# Crowtail-_LoRa_RA-08H-V1_2.net
KiCad netlist of a schematic drawn in EAGLE
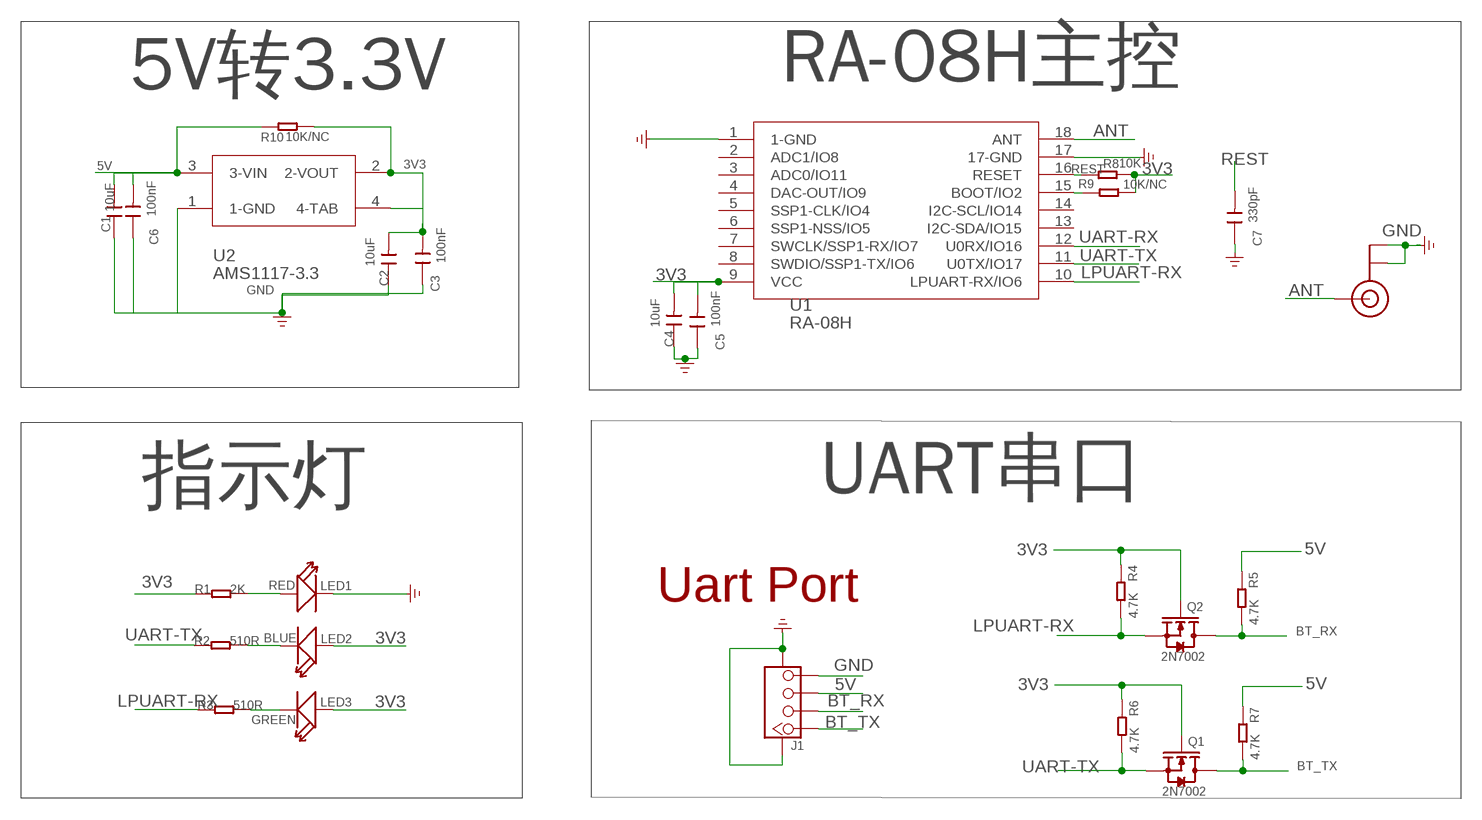
[diagram p0: schematic, sheet 1]

(export (version "E")
  (design (tool "Eeschema 10.0.6"))
  (components
    (comp (ref "C1")
      (value "10uF")
      (footprint "eagle-import:C0805")
      (libsource (lib "eagle-import") (part "C-0805"))
    )
    (comp (ref "C2")
      (value "10uF")
      (footprint "eagle-import:C0805")
      (libsource (lib "eagle-import") (part "C-0805"))
    )
    (comp (ref "C3")
      (value "100nF")
      (footprint "eagle-import:C0603")
      (libsource (lib "eagle-import") (part "C-0603"))
    )
    (comp (ref "C4")
      (value "10uF")
      (footprint "eagle-import:C0805")
      (libsource (lib "eagle-import") (part "C-0805"))
    )
    (comp (ref "C5")
      (value "100nF")
      (footprint "eagle-import:C0603")
      (libsource (lib "eagle-import") (part "C-0603"))
    )
    (comp (ref "C6")
      (value "100nF")
      (footprint "eagle-import:C0603")
      (libsource (lib "eagle-import") (part "C-0603"))
    )
    (comp (ref "C7")
      (value "330pF")
      (footprint "eagle-import:C0603")
      (libsource (lib "eagle-import") (part "C-0603"))
    )
    (comp (ref "J1")
      (value "TWIG-4P-2.0-SMD-FEMALE-REINFORCE'90D'")
      (footprint "eagle-import:4P-SMD-2.0-90D")
      (libsource (lib "eagle-import") (part "TWIG-4P-2.0-SMD-FEMALE-REINFORCE'90D'"))
    )
    (comp (ref "J2")
      (value "U.FL")
      (footprint "eagle-import:U.FL")
      (libsource (lib "eagle-import") (part "U.FL"))
    )
    (comp (ref "LED1")
      (value "RED")
      (footprint "eagle-import:LED-0603")
      (libsource (lib "eagle-import") (part "LED'0603'"))
    )
    (comp (ref "LED2")
      (value "BLUE")
      (footprint "eagle-import:LED-0603")
      (libsource (lib "eagle-import") (part "LED'0603'"))
    )
    (comp (ref "LED3")
      (value "GREEN")
      (footprint "eagle-import:LED-0603")
      (libsource (lib "eagle-import") (part "LED'0603'"))
    )
    (comp (ref "Q1")
      (value "2N7002")
      (footprint "eagle-import:SOT23")
      (libsource (lib "eagle-import") (part "MOSFET-N'SOT23'"))
    )
    (comp (ref "Q2")
      (value "2N7002")
      (footprint "eagle-import:SOT23")
      (libsource (lib "eagle-import") (part "MOSFET-N'SOT23'"))
    )
    (comp (ref "R1")
      (value "2K")
      (footprint "eagle-import:0603")
      (libsource (lib "eagle-import") (part "R-0603"))
    )
    (comp (ref "R2")
      (value "510R")
      (footprint "eagle-import:0603")
      (libsource (lib "eagle-import") (part "R-0603"))
    )
    (comp (ref "R3")
      (value "510R")
      (footprint "eagle-import:0603")
      (libsource (lib "eagle-import") (part "R-0603"))
    )
    (comp (ref "R4")
      (value "4.7K")
      (footprint "eagle-import:DISCRETE_R0603")
      (libsource (lib "eagle-import") (part "DISCRETE_R-0603"))
    )
    (comp (ref "R5")
      (value "4.7K")
      (footprint "eagle-import:DISCRETE_R0603")
      (libsource (lib "eagle-import") (part "DISCRETE_R-0603"))
    )
    (comp (ref "R6")
      (value "4.7K")
      (footprint "eagle-import:DISCRETE_R0603")
      (libsource (lib "eagle-import") (part "DISCRETE_R-0603"))
    )
    (comp (ref "R7")
      (value "4.7K")
      (footprint "eagle-import:DISCRETE_R0603")
      (libsource (lib "eagle-import") (part "DISCRETE_R-0603"))
    )
    (comp (ref "R8")
      (value "10K")
      (footprint "eagle-import:DISCRETE_R0603")
      (libsource (lib "eagle-import") (part "DISCRETE_R-0603"))
    )
    (comp (ref "R9")
      (value "10K/NC")
      (footprint "eagle-import:DISCRETE_R0603")
      (libsource (lib "eagle-import") (part "DISCRETE_R-0603"))
    )
    (comp (ref "R10")
      (value "10K/NC")
      (footprint "eagle-import:DISCRETE_R0603")
      (libsource (lib "eagle-import") (part "DISCRETE_R-0603"))
    )
    (comp (ref "U1")
      (value "RA-08H")
      (footprint "eagle-import:RA-08H-SMD-18")
      (libsource (lib "eagle-import") (part "RA-08H"))
    )
    (comp (ref "U2")
      (value "AMS1117-3.3")
      (footprint "eagle-import:AMS1117-3.3-SOT223")
      (libsource (lib "eagle-import") (part "AMS1117-3.3"))
    )
  )
  (nets
    (net (code "1") (name "/3V3") (class "Default")
      (node (ref "C2") (pin "2") (pinfunction "2_2") (pintype "passive"))
      (node (ref "C3") (pin "2") (pinfunction "2_2") (pintype "passive"))
      (node (ref "C4") (pin "2") (pinfunction "2_2") (pintype "passive"))
      (node (ref "C5") (pin "2") (pinfunction "2_2") (pintype "passive"))
      (node (ref "LED2") (pin "+") (pinfunction "+_+") (pintype "passive"))
      (node (ref "LED3") (pin "+") (pinfunction "+_+") (pintype "passive"))
      (node (ref "Q1") (pin "1") (pinfunction "G_1") (pintype "passive"))
      (node (ref "Q2") (pin "1") (pinfunction "G_1") (pintype "passive"))
      (node (ref "R1") (pin "1") (pinfunction "1_1") (pintype "passive"))
      (node (ref "R10") (pin "2") (pinfunction "2_2") (pintype "passive"))
      (node (ref "R4") (pin "1") (pinfunction "1_1") (pintype "passive"))
      (node (ref "R6") (pin "1") (pinfunction "1_1") (pintype "passive"))
      (node (ref "R8") (pin "2") (pinfunction "2_2") (pintype "passive"))
      (node (ref "R9") (pin "2") (pinfunction "2_2") (pintype "passive"))
      (node (ref "U1") (pin "9") (pinfunction "VCC_9") (pintype "bidirectional"))
      (node (ref "U2") (pin "2") (pinfunction "2-VOUT_2") (pintype "bidirectional"))
      (node (ref "U2") (pin "4") (pinfunction "4-TAB_4") (pintype "bidirectional"))
    )
    (net (code "2") (name "/5V") (class "Default")
      (node (ref "C1") (pin "2") (pinfunction "2_2") (pintype "passive"))
      (node (ref "C6") (pin "2") (pinfunction "2_2") (pintype "passive"))
      (node (ref "J1") (pin "3") (pinfunction "3_3") (pintype "bidirectional"))
      (node (ref "R10") (pin "1") (pinfunction "1_1") (pintype "passive"))
      (node (ref "R5") (pin "1") (pinfunction "1_1") (pintype "passive"))
      (node (ref "R7") (pin "1") (pinfunction "1_1") (pintype "passive"))
      (node (ref "U2") (pin "3") (pinfunction "3-VIN_3") (pintype "bidirectional"))
    )
    (net (code "3") (name "/ANT") (class "Default")
      (node (ref "J2") (pin "P$3") (pinfunction "SIGNAL_P$3") (pintype "bidirectional"))
      (node (ref "U1") (pin "18") (pinfunction "ANT_18") (pintype "bidirectional"))
    )
    (net (code "4") (name "/BT_RX") (class "Default")
      (node (ref "J1") (pin "2") (pinfunction "2_2") (pintype "bidirectional"))
      (node (ref "Q2") (pin "3") (pinfunction "D_3") (pintype "passive"))
      (node (ref "R5") (pin "2") (pinfunction "2_2") (pintype "passive"))
    )
    (net (code "5") (name "/BT_TX") (class "Default")
      (node (ref "J1") (pin "1") (pinfunction "1_1") (pintype "bidirectional"))
      (node (ref "Q1") (pin "3") (pinfunction "D_3") (pintype "passive"))
      (node (ref "R7") (pin "2") (pinfunction "2_2") (pintype "passive"))
    )
    (net (code "6") (name "/LPUART-RX") (class "Default")
      (node (ref "Q2") (pin "2") (pinfunction "S_2") (pintype "passive"))
      (node (ref "R3") (pin "1") (pinfunction "1_1") (pintype "passive"))
      (node (ref "R4") (pin "2") (pinfunction "2_2") (pintype "passive"))
      (node (ref "U1") (pin "10") (pinfunction "LPUART-RX/IO6_10") (pintype "bidirectional"))
    )
    (net (code "7") (name "/REST") (class "Default")
      (node (ref "C7") (pin "2") (pinfunction "2_2") (pintype "passive"))
      (node (ref "R8") (pin "1") (pinfunction "1_1") (pintype "passive"))
      (node (ref "U1") (pin "16") (pinfunction "RESET_16") (pintype "bidirectional"))
    )
    (net (code "8") (name "/UART-RX") (class "Default")
      (node (ref "U1") (pin "12") (pinfunction "U0RX/IO16_12") (pintype "bidirectional"))
    )
    (net (code "9") (name "/UART-TX") (class "Default")
      (node (ref "Q1") (pin "2") (pinfunction "S_2") (pintype "passive"))
      (node (ref "R2") (pin "1") (pinfunction "1_1") (pintype "passive"))
      (node (ref "R6") (pin "2") (pinfunction "2_2") (pintype "passive"))
      (node (ref "U1") (pin "11") (pinfunction "U0TX/IO17_11") (pintype "bidirectional"))
    )
    (net (code "10") (name "GND_POWER") (class "Default")
      (node (ref "C1") (pin "1") (pinfunction "1_1") (pintype "passive"))
      (node (ref "C2") (pin "1") (pinfunction "1_1") (pintype "passive"))
      (node (ref "C3") (pin "1") (pinfunction "1_1") (pintype "passive"))
      (node (ref "C4") (pin "1") (pinfunction "1_1") (pintype "passive"))
      (node (ref "C5") (pin "1") (pinfunction "1_1") (pintype "passive"))
      (node (ref "C6") (pin "1") (pinfunction "1_1") (pintype "passive"))
      (node (ref "C7") (pin "1") (pinfunction "1_1") (pintype "passive"))
      (node (ref "J1") (pin "4") (pinfunction "4_4") (pintype "bidirectional"))
      (node (ref "J1") (pin "SS1") (pinfunction "SS1_SS1") (pintype "bidirectional"))
      (node (ref "J1") (pin "SS2") (pinfunction "SS2_SS2") (pintype "bidirectional"))
      (node (ref "J2") (pin "P$1") (pinfunction "GND_P$1") (pintype "bidirectional"))
      (node (ref "J2") (pin "P$2") (pinfunction "GND_P$2") (pintype "bidirectional"))
      (node (ref "LED1") (pin "-") (pinfunction "-_-") (pintype "passive"))
      (node (ref "U1") (pin "1") (pinfunction "1-GND_1") (pintype "bidirectional"))
      (node (ref "U1") (pin "17") (pinfunction "17-GND_17") (pintype "bidirectional"))
      (node (ref "U2") (pin "1") (pinfunction "1-GND_1") (pintype "bidirectional"))
    )
    (net (code "11") (name "Net-(LED1-Pad+)") (class "Default")
      (node (ref "LED1") (pin "+") (pinfunction "+_+") (pintype "passive"))
      (node (ref "R1") (pin "2") (pinfunction "2_2") (pintype "passive"))
    )
    (net (code "12") (name "Net-(LED2-Pad-)") (class "Default")
      (node (ref "LED2") (pin "-") (pinfunction "-_-") (pintype "passive"))
      (node (ref "R2") (pin "2") (pinfunction "2_2") (pintype "passive"))
    )
    (net (code "13") (name "Net-(LED3-Pad-)") (class "Default")
      (node (ref "LED3") (pin "-") (pinfunction "-_-") (pintype "passive"))
      (node (ref "R3") (pin "2") (pinfunction "2_2") (pintype "passive"))
    )
    (net (code "14") (name "Net-(U1-BOOT{slash}IO2)") (class "Default")
      (node (ref "R9") (pin "1") (pinfunction "1_1") (pintype "passive"))
      (node (ref "U1") (pin "15") (pinfunction "BOOT/IO2_15") (pintype "bidirectional"))
    )
    (net (code "15") (name "unconnected-(U1-ADC0{slash}IO11-Pad3)") (class "Default")
      (node (ref "U1") (pin "3") (pinfunction "ADC0/IO11_3") (pintype "bidirectional"))
    )
    (net (code "16") (name "unconnected-(U1-ADC1{slash}IO8-Pad2)") (class "Default")
      (node (ref "U1") (pin "2") (pinfunction "ADC1/IO8_2") (pintype "bidirectional"))
    )
    (net (code "17") (name "unconnected-(U1-DAC-OUT{slash}IO9-Pad4)") (class "Default")
      (node (ref "U1") (pin "4") (pinfunction "DAC-OUT/IO9_4") (pintype "bidirectional"))
    )
    (net (code "18") (name "unconnected-(U1-I2C-SCL{slash}IO14-Pad14)") (class "Default")
      (node (ref "U1") (pin "14") (pinfunction "I2C-SCL/IO14_14") (pintype "bidirectional"))
    )
    (net (code "19") (name "unconnected-(U1-I2C-SDA{slash}IO15-Pad13)") (class "Default")
      (node (ref "U1") (pin "13") (pinfunction "I2C-SDA/IO15_13") (pintype "bidirectional"))
    )
    (net (code "20") (name "unconnected-(U1-SSP1-CLK{slash}IO4-Pad5)") (class "Default")
      (node (ref "U1") (pin "5") (pinfunction "SSP1-CLK/IO4_5") (pintype "bidirectional"))
    )
    (net (code "21") (name "unconnected-(U1-SSP1-NSS{slash}IO5-Pad6)") (class "Default")
      (node (ref "U1") (pin "6") (pinfunction "SSP1-NSS/IO5_6") (pintype "bidirectional"))
    )
    (net (code "22") (name "unconnected-(U1-SWCLK{slash}SSP1-RX{slash}IO7-Pad7)") (class "Default")
      (node (ref "U1") (pin "7") (pinfunction "SWCLK/SSP1-RX/IO7_7") (pintype "bidirectional"))
    )
    (net (code "23") (name "unconnected-(U1-SWDIO{slash}SSP1-TX{slash}IO6-Pad8)") (class "Default")
      (node (ref "U1") (pin "8") (pinfunction "SWDIO/SSP1-TX/IO6_8") (pintype "bidirectional"))
    )
  )
)
